# breakout_v3.net
KiCad netlist of a schematic drawn in EAGLE
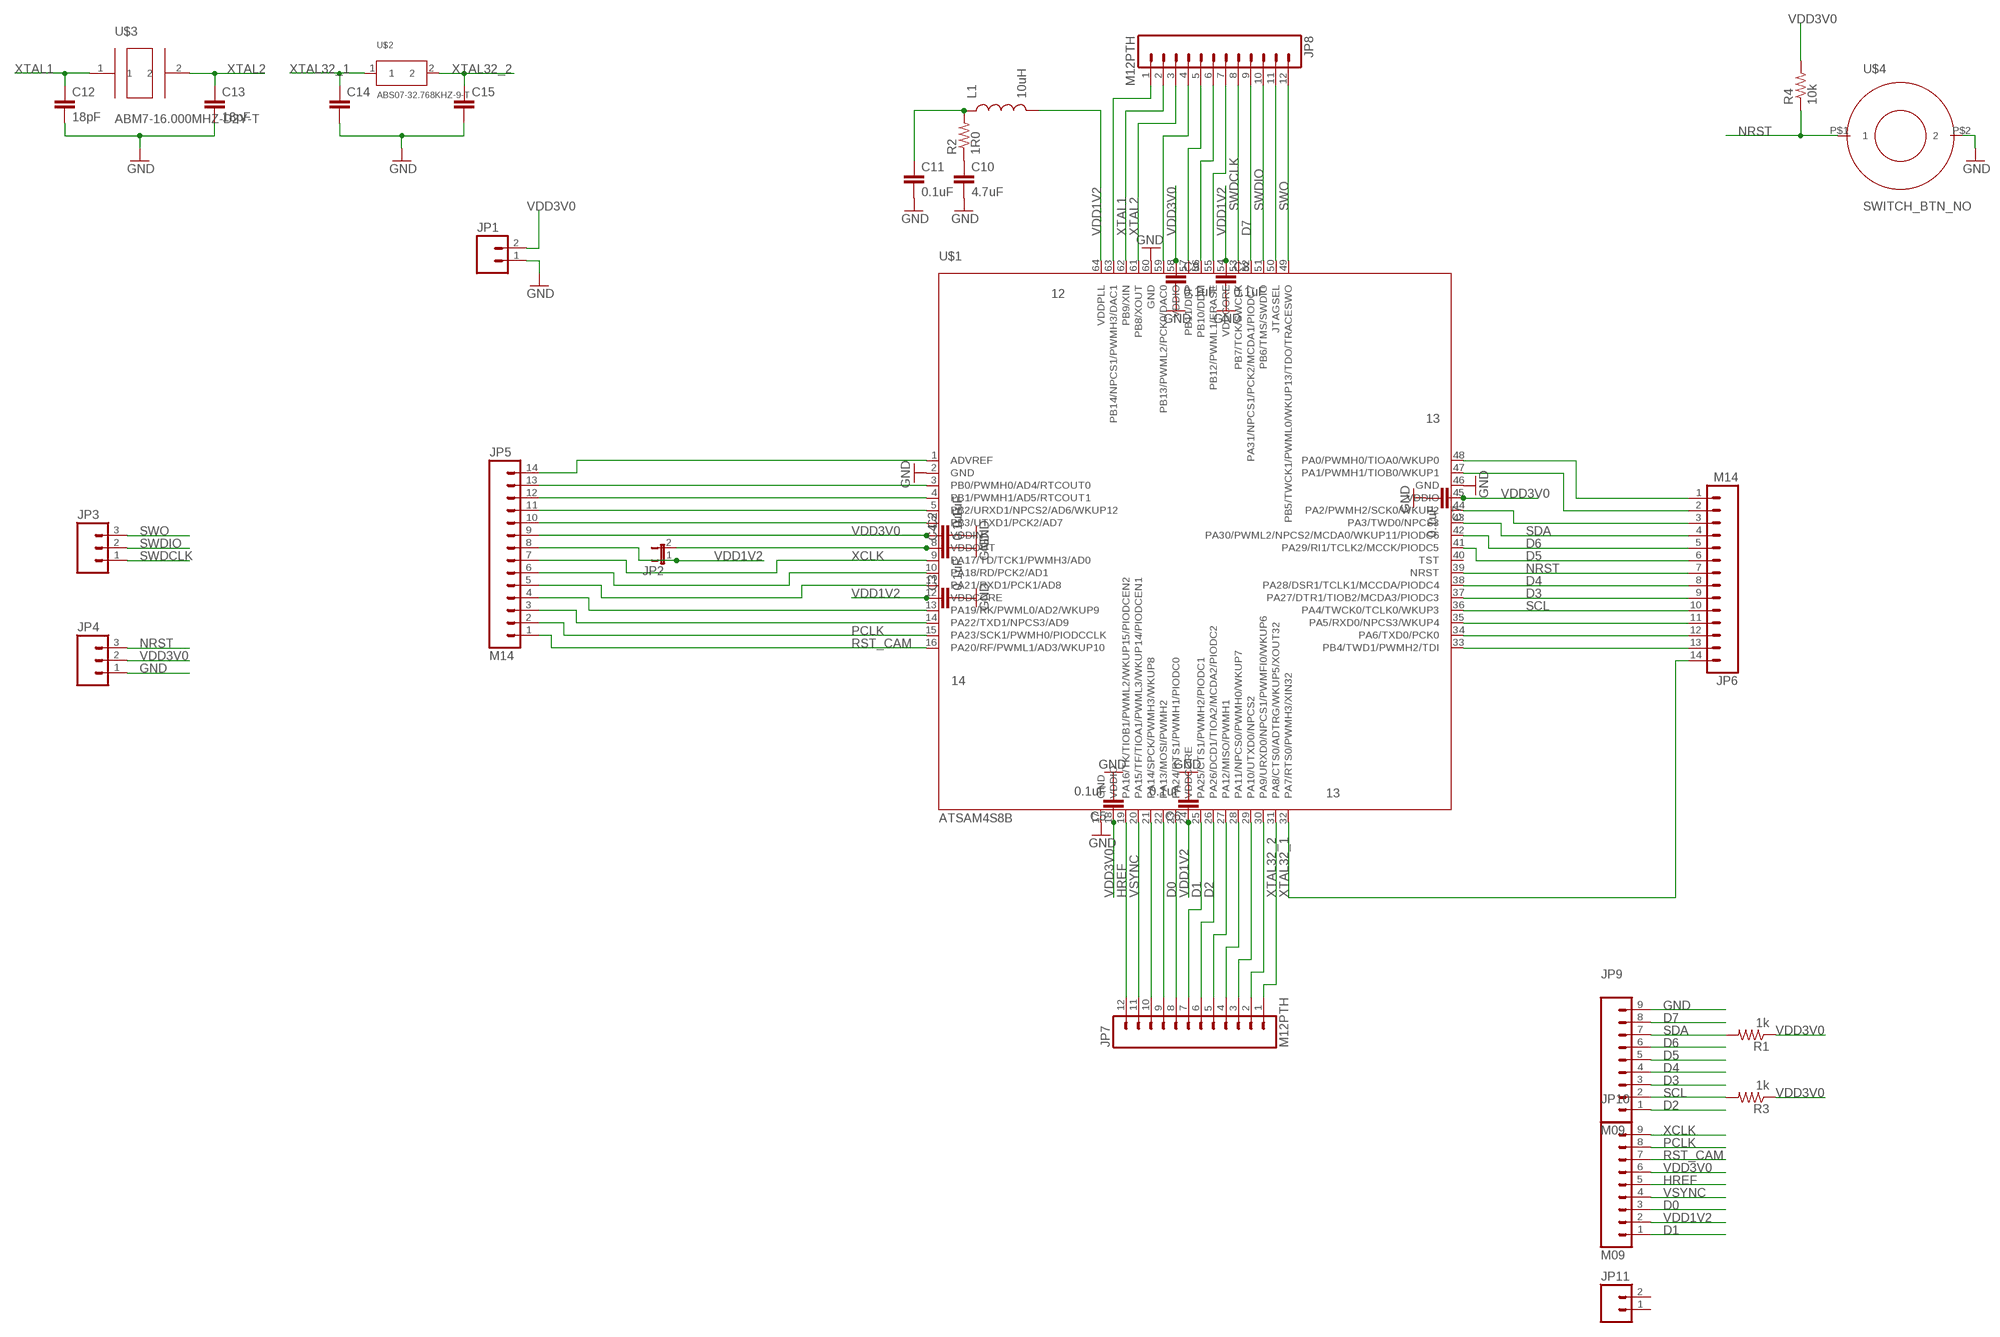
[diagram p0: schematic, sheet 1]

(export (version "E")
  (design (tool "Eeschema 10.0.6"))
  (components
    (comp (ref "C2")
      (value "0.1uF")
      (footprint "eagle-import:0805")
      (libsource (lib "eagle-import") (part "CAP0805"))
    )
    (comp (ref "C3")
      (value "0.1uF")
      (footprint "eagle-import:0805")
      (libsource (lib "eagle-import") (part "CAP0805"))
    )
    (comp (ref "C4")
      (value "0.1uF")
      (footprint "eagle-import:0805")
      (libsource (lib "eagle-import") (part "CAP0805"))
    )
    (comp (ref "C5")
      (value "0.1uF")
      (footprint "eagle-import:0805")
      (libsource (lib "eagle-import") (part "CAP0805"))
    )
    (comp (ref "C6")
      (value "0.1uF")
      (footprint "eagle-import:0805")
      (libsource (lib "eagle-import") (part "CAP0805"))
    )
    (comp (ref "C7")
      (value "0.1uF")
      (footprint "eagle-import:0805")
      (libsource (lib "eagle-import") (part "CAP0805"))
    )
    (comp (ref "C8")
      (value "0.1uF")
      (footprint "eagle-import:0805")
      (libsource (lib "eagle-import") (part "CAP0805"))
    )
    (comp (ref "C9")
      (value "0.1uF")
      (footprint "eagle-import:0805")
      (libsource (lib "eagle-import") (part "CAP0805"))
    )
    (comp (ref "C10")
      (value "4.7uF")
      (footprint "eagle-import:0805")
      (libsource (lib "eagle-import") (part "CAP0805"))
    )
    (comp (ref "C11")
      (value "0.1uF")
      (footprint "eagle-import:0805")
      (libsource (lib "eagle-import") (part "CAP0805"))
    )
    (comp (ref "C12")
      (value "18pF")
      (footprint "eagle-import:0805")
      (libsource (lib "eagle-import") (part "CAP0805"))
    )
    (comp (ref "C13")
      (value "18pF")
      (footprint "eagle-import:0805")
      (libsource (lib "eagle-import") (part "CAP0805"))
    )
    (comp (ref "C14")
      (value "CAP0805")
      (footprint "eagle-import:0805")
      (libsource (lib "eagle-import") (part "CAP0805"))
    )
    (comp (ref "C15")
      (value "CAP0805")
      (footprint "eagle-import:0805")
      (libsource (lib "eagle-import") (part "CAP0805"))
    )
    (comp (ref "JP1")
      (value "M02PTH")
      (footprint "eagle-import:1X02")
      (libsource (lib "eagle-import") (part "M02PTH"))
    )
    (comp (ref "JP2")
      (value "JUMPER-2PTH")
      (footprint "eagle-import:1X02")
      (libsource (lib "eagle-import") (part "JUMPER-2PTH"))
    )
    (comp (ref "JP3")
      (value "M03PTH")
      (footprint "eagle-import:1X03")
      (libsource (lib "eagle-import") (part "M03PTH"))
    )
    (comp (ref "JP4")
      (value "M03PTH")
      (footprint "eagle-import:1X03")
      (libsource (lib "eagle-import") (part "M03PTH"))
    )
    (comp (ref "JP5")
      (value "M14")
      (footprint "eagle-import:1X14")
      (libsource (lib "eagle-import") (part "M14"))
    )
    (comp (ref "JP6")
      (value "M14")
      (footprint "eagle-import:1X14")
      (libsource (lib "eagle-import") (part "M14"))
    )
    (comp (ref "JP7")
      (value "M12PTH")
      (footprint "eagle-import:1X12")
      (libsource (lib "eagle-import") (part "M12PTH"))
    )
    (comp (ref "JP8")
      (value "M12PTH")
      (footprint "eagle-import:1X12")
      (libsource (lib "eagle-import") (part "M12PTH"))
    )
    (comp (ref "JP9")
      (value "M09")
      (footprint "eagle-import:1X09")
      (libsource (lib "eagle-import") (part "M09"))
    )
    (comp (ref "JP10")
      (value "M09")
      (footprint "eagle-import:1X09")
      (libsource (lib "eagle-import") (part "M09"))
    )
    (comp (ref "JP11")
      (value "M02PTH")
      (footprint "eagle-import:1X02")
      (libsource (lib "eagle-import") (part "M02PTH"))
    )
    (comp (ref "L1")
      (value "10uH")
      (footprint "eagle-import:0805")
      (libsource (lib "eagle-import") (part "INDUCTOR0805"))
    )
    (comp (ref "R1")
      (value "1k")
      (footprint "eagle-import:0805")
      (libsource (lib "eagle-import") (part "RESISTOR0805-RES"))
    )
    (comp (ref "R2")
      (value "1R0")
      (footprint "eagle-import:0805")
      (libsource (lib "eagle-import") (part "RESISTOR0805-RES"))
    )
    (comp (ref "R3")
      (value "1k")
      (footprint "eagle-import:0805")
      (libsource (lib "eagle-import") (part "RESISTOR0805-RES"))
    )
    (comp (ref "R4")
      (value "10k")
      (footprint "eagle-import:0805")
      (libsource (lib "eagle-import") (part "RES"))
    )
    (comp (ref "U$1")
      (value "ATSAM4S8B")
      (footprint "eagle-import:QFP50P1200X1200X160-64N")
      (libsource (lib "eagle-import") (part "ATSAM4S8B"))
    )
    (comp (ref "U$2")
      (value "ABS07-32.768KHZ-9-T")
      (footprint "eagle-import:ABS07-32.768KHZ-9-T")
      (libsource (lib "eagle-import") (part "ABS07-32.768KHZ-9-T"))
    )
    (comp (ref "U$3")
      (value "ABM7-16.000MHZ-D2Y-T")
      (footprint "eagle-import:ABM7-16.000MHZ-D2Y-T")
      (libsource (lib "eagle-import") (part "ABM7-16.000MHZ-D2Y-T"))
    )
    (comp (ref "U$4")
      (value "SWITCH_BTN_NO")
      (footprint "eagle-import:BTN_2")
      (libsource (lib "eagle-import") (part "SWITCH_BTN_NO"))
    )
  )
  (nets
    (net (code "1") (name "/D0") (class "Default")
      (node (ref "JP10") (pin "3") (pinfunction "3_3") (pintype "passive"))
      (node (ref "JP7") (pin "8") (pinfunction "8_8") (pintype "passive"))
      (node (ref "U$1") (pin "23") (pinfunction "PA24/RTS1/PWMH1/PIODC0_23") (pintype "bidirectional"))
    )
    (net (code "2") (name "/D1") (class "Default")
      (node (ref "JP10") (pin "1") (pinfunction "1_1") (pintype "passive"))
      (node (ref "JP7") (pin "7") (pinfunction "7_7") (pintype "passive"))
      (node (ref "U$1") (pin "25") (pinfunction "PA25/CTS1/PWMH2/PIODC1_25") (pintype "bidirectional"))
    )
    (net (code "3") (name "/D2") (class "Default")
      (node (ref "JP7") (pin "6") (pinfunction "6_6") (pintype "passive"))
      (node (ref "JP9") (pin "1") (pinfunction "1_1") (pintype "passive"))
      (node (ref "U$1") (pin "26") (pinfunction "PA26/DCD1/TIOA2/MCDA2/PIODC2_26") (pintype "bidirectional"))
    )
    (net (code "4") (name "/D3") (class "Default")
      (node (ref "JP6") (pin "9") (pinfunction "9_9") (pintype "passive"))
      (node (ref "JP9") (pin "3") (pinfunction "3_3") (pintype "passive"))
      (node (ref "U$1") (pin "37") (pinfunction "PA27/DTR1/TIOB2/MCDA3/PIODC3_37") (pintype "bidirectional"))
    )
    (net (code "5") (name "/D4") (class "Default")
      (node (ref "JP6") (pin "8") (pinfunction "8_8") (pintype "passive"))
      (node (ref "JP9") (pin "4") (pinfunction "4_4") (pintype "passive"))
      (node (ref "U$1") (pin "38") (pinfunction "PA28/DSR1/TCLK1/MCCDA/PIODC4_38") (pintype "bidirectional"))
    )
    (net (code "6") (name "/D5") (class "Default")
      (node (ref "JP6") (pin "6") (pinfunction "6_6") (pintype "passive"))
      (node (ref "JP9") (pin "5") (pinfunction "5_5") (pintype "passive"))
      (node (ref "U$1") (pin "41") (pinfunction "PA29/RI1/TCLK2/MCCK/PIODC5_41") (pintype "bidirectional"))
    )
    (net (code "7") (name "/D6") (class "Default")
      (node (ref "JP6") (pin "5") (pinfunction "5_5") (pintype "passive"))
      (node (ref "JP9") (pin "6") (pinfunction "6_6") (pintype "passive"))
      (node (ref "U$1") (pin "42") (pinfunction "PA30/PWML2/NPCS2/MCDA0/WKUP11/PIODC6_42") (pintype "bidirectional"))
    )
    (net (code "8") (name "/D7") (class "Default")
      (node (ref "JP8") (pin "9") (pinfunction "9_9") (pintype "passive"))
      (node (ref "JP9") (pin "8") (pinfunction "8_8") (pintype "passive"))
      (node (ref "U$1") (pin "52") (pinfunction "PA31/NPCS1/PCK2/MCDA1/PIODC7_52") (pintype "bidirectional"))
    )
    (net (code "9") (name "/HREF") (class "Default")
      (node (ref "JP10") (pin "5") (pinfunction "5_5") (pintype "passive"))
      (node (ref "JP7") (pin "12") (pinfunction "12_12") (pintype "passive"))
      (node (ref "U$1") (pin "19") (pinfunction "PA16/TK/TIOB1/PWML2/WKUP15/PIODCEN2_19") (pintype "bidirectional"))
    )
    (net (code "10") (name "/NRST") (class "Default")
      (node (ref "JP4") (pin "3") (pinfunction "3_3") (pintype "passive"))
      (node (ref "JP6") (pin "7") (pinfunction "7_7") (pintype "passive"))
      (node (ref "R4") (pin "1") (pinfunction "1_1") (pintype "passive"))
      (node (ref "U$1") (pin "39") (pinfunction "NRST_39") (pintype "bidirectional"))
      (node (ref "U$4") (pin "P$1") (pinfunction "1_P$1") (pintype "bidirectional"))
    )
    (net (code "11") (name "/PCLK") (class "Default")
      (node (ref "JP10") (pin "8") (pinfunction "8_8") (pintype "passive"))
      (node (ref "JP5") (pin "2") (pinfunction "2_2") (pintype "passive"))
      (node (ref "U$1") (pin "15") (pinfunction "PA23/SCK1/PWMH0/PIODCCLK_15") (pintype "bidirectional"))
    )
    (net (code "12") (name "/RST_CAM") (class "Default")
      (node (ref "JP10") (pin "7") (pinfunction "7_7") (pintype "passive"))
      (node (ref "JP5") (pin "1") (pinfunction "1_1") (pintype "passive"))
      (node (ref "U$1") (pin "16") (pinfunction "PA20/RF/PWML1/AD3/WKUP10_16") (pintype "bidirectional"))
    )
    (net (code "13") (name "/SCL") (class "Default")
      (node (ref "JP6") (pin "10") (pinfunction "10_10") (pintype "passive"))
      (node (ref "JP9") (pin "2") (pinfunction "2_2") (pintype "passive"))
      (node (ref "R3") (pin "2") (pinfunction "2_2") (pintype "passive"))
      (node (ref "U$1") (pin "36") (pinfunction "PA4/TWCK0/TCLK0/WKUP3_36") (pintype "bidirectional"))
    )
    (net (code "14") (name "/SDA") (class "Default")
      (node (ref "JP6") (pin "4") (pinfunction "4_4") (pintype "passive"))
      (node (ref "JP9") (pin "7") (pinfunction "7_7") (pintype "passive"))
      (node (ref "R1") (pin "2") (pinfunction "2_2") (pintype "passive"))
      (node (ref "U$1") (pin "43") (pinfunction "PA3/TWD0/NPCS3_43") (pintype "bidirectional"))
    )
    (net (code "15") (name "/SWDCLK") (class "Default")
      (node (ref "JP3") (pin "1") (pinfunction "1_1") (pintype "passive"))
      (node (ref "JP8") (pin "8") (pinfunction "8_8") (pintype "passive"))
      (node (ref "U$1") (pin "53") (pinfunction "PB7/TCK/SWCLK_53") (pintype "bidirectional"))
    )
    (net (code "16") (name "/SWDIO") (class "Default")
      (node (ref "JP3") (pin "2") (pinfunction "2_2") (pintype "passive"))
      (node (ref "JP8") (pin "10") (pinfunction "10_10") (pintype "passive"))
      (node (ref "U$1") (pin "51") (pinfunction "PB6/TMS/SWDIO_51") (pintype "bidirectional"))
    )
    (net (code "17") (name "/SWO") (class "Default")
      (node (ref "JP3") (pin "3") (pinfunction "3_3") (pintype "passive"))
      (node (ref "JP8") (pin "12") (pinfunction "12_12") (pintype "passive"))
      (node (ref "U$1") (pin "49") (pinfunction "PB5/TWCK1/PWML0/WKUP13/TDO/TRACESWO_49") (pintype "bidirectional"))
    )
    (net (code "18") (name "/VDD1V2") (class "Default")
      (node (ref "C3") (pin "1") (pinfunction "1_1") (pintype "passive"))
      (node (ref "C6") (pin "1") (pinfunction "1_1") (pintype "passive"))
      (node (ref "C8") (pin "1") (pinfunction "1_1") (pintype "passive"))
      (node (ref "JP10") (pin "2") (pinfunction "2_2") (pintype "passive"))
      (node (ref "JP2") (pin "1") (pinfunction "1_1") (pintype "passive"))
      (node (ref "JP5") (pin "8") (pinfunction "8_8") (pintype "passive"))
      (node (ref "L1") (pin "2") (pinfunction "2_2") (pintype "passive"))
      (node (ref "U$1") (pin "12") (pinfunction "VDDCORE_12") (pintype "bidirectional"))
      (node (ref "U$1") (pin "24") (pinfunction "VDDCORE_24") (pintype "bidirectional"))
      (node (ref "U$1") (pin "54") (pinfunction "VDDCORE_54") (pintype "bidirectional"))
      (node (ref "U$1") (pin "64") (pinfunction "VDDPLL_64") (pintype "bidirectional"))
    )
    (net (code "19") (name "/VDD3V0") (class "Default")
      (node (ref "C2") (pin "1") (pinfunction "1_1") (pintype "passive"))
      (node (ref "C5") (pin "1") (pinfunction "1_1") (pintype "passive"))
      (node (ref "C7") (pin "1") (pinfunction "1_1") (pintype "passive"))
      (node (ref "C9") (pin "1") (pinfunction "1_1") (pintype "passive"))
      (node (ref "JP1") (pin "2") (pinfunction "2_2") (pintype "passive"))
      (node (ref "JP10") (pin "6") (pinfunction "6_6") (pintype "passive"))
      (node (ref "JP4") (pin "2") (pinfunction "2_2") (pintype "passive"))
      (node (ref "JP5") (pin "9") (pinfunction "9_9") (pintype "passive"))
      (node (ref "R1") (pin "1") (pinfunction "1_1") (pintype "passive"))
      (node (ref "R3") (pin "1") (pinfunction "1_1") (pintype "passive"))
      (node (ref "R4") (pin "2") (pinfunction "2_2") (pintype "passive"))
      (node (ref "U$1") (pin "18") (pinfunction "VDDIO_18") (pintype "bidirectional"))
      (node (ref "U$1") (pin "45") (pinfunction "VDDIO_45") (pintype "bidirectional"))
      (node (ref "U$1") (pin "58") (pinfunction "VDDIO_58") (pintype "bidirectional"))
      (node (ref "U$1") (pin "7") (pinfunction "VDDIN_7") (pintype "bidirectional"))
    )
    (net (code "20") (name "/VSYNC") (class "Default")
      (node (ref "JP10") (pin "4") (pinfunction "4_4") (pintype "passive"))
      (node (ref "JP7") (pin "11") (pinfunction "11_11") (pintype "passive"))
      (node (ref "U$1") (pin "20") (pinfunction "PA15/TF/TIOA1/PWML3/WKUP14/PIODCEN1_20") (pintype "bidirectional"))
    )
    (net (code "21") (name "/XCLK") (class "Default")
      (node (ref "JP10") (pin "9") (pinfunction "9_9") (pintype "passive"))
      (node (ref "JP5") (pin "7") (pinfunction "7_7") (pintype "passive"))
      (node (ref "U$1") (pin "9") (pinfunction "PA17/TD/TCK1/PWMH3/AD0_9") (pintype "bidirectional"))
    )
    (net (code "22") (name "/XTAL1") (class "Default")
      (node (ref "C12") (pin "1") (pinfunction "1_1") (pintype "passive"))
      (node (ref "JP8") (pin "2") (pinfunction "2_2") (pintype "passive"))
      (node (ref "U$1") (pin "62") (pinfunction "PB9/XIN_62") (pintype "bidirectional"))
      (node (ref "U$3") (pin "1") (pinfunction "1_1") (pintype "bidirectional"))
    )
    (net (code "23") (name "/XTAL2") (class "Default")
      (node (ref "C13") (pin "1") (pinfunction "1_1") (pintype "passive"))
      (node (ref "JP8") (pin "3") (pinfunction "3_3") (pintype "passive"))
      (node (ref "U$1") (pin "61") (pinfunction "PB8/XOUT_61") (pintype "bidirectional"))
      (node (ref "U$3") (pin "2") (pinfunction "2_2") (pintype "bidirectional"))
    )
    (net (code "24") (name "/XTAL32_1") (class "Default")
      (node (ref "C14") (pin "1") (pinfunction "1_1") (pintype "passive"))
      (node (ref "JP6") (pin "14") (pinfunction "14_14") (pintype "passive"))
      (node (ref "U$1") (pin "32") (pinfunction "PA7/RTS0/PWMH3/XIN32_32") (pintype "bidirectional"))
      (node (ref "U$2") (pin "1") (pinfunction "1_1") (pintype "bidirectional"))
    )
    (net (code "25") (name "/XTAL32_2") (class "Default")
      (node (ref "C15") (pin "1") (pinfunction "1_1") (pintype "passive"))
      (node (ref "JP7") (pin "1") (pinfunction "1_1") (pintype "passive"))
      (node (ref "U$1") (pin "31") (pinfunction "PA8/CTS0/ADTRG/WKUP5/XOUT32_31") (pintype "bidirectional"))
      (node (ref "U$2") (pin "2") (pinfunction "2_2") (pintype "bidirectional"))
    )
    (net (code "26") (name "GND") (class "Default")
      (node (ref "C10") (pin "2") (pinfunction "2_2") (pintype "passive"))
      (node (ref "C11") (pin "2") (pinfunction "2_2") (pintype "passive"))
      (node (ref "C12") (pin "2") (pinfunction "2_2") (pintype "passive"))
      (node (ref "C13") (pin "2") (pinfunction "2_2") (pintype "passive"))
      (node (ref "C14") (pin "2") (pinfunction "2_2") (pintype "passive"))
      (node (ref "C15") (pin "2") (pinfunction "2_2") (pintype "passive"))
      (node (ref "C2") (pin "2") (pinfunction "2_2") (pintype "passive"))
      (node (ref "C3") (pin "2") (pinfunction "2_2") (pintype "passive"))
      (node (ref "C4") (pin "2") (pinfunction "2_2") (pintype "passive"))
      (node (ref "C5") (pin "2") (pinfunction "2_2") (pintype "passive"))
      (node (ref "C6") (pin "2") (pinfunction "2_2") (pintype "passive"))
      (node (ref "C7") (pin "2") (pinfunction "2_2") (pintype "passive"))
      (node (ref "C8") (pin "2") (pinfunction "2_2") (pintype "passive"))
      (node (ref "C9") (pin "2") (pinfunction "2_2") (pintype "passive"))
      (node (ref "JP1") (pin "1") (pinfunction "1_1") (pintype "passive"))
      (node (ref "JP4") (pin "1") (pinfunction "1_1") (pintype "passive"))
      (node (ref "JP9") (pin "9") (pinfunction "9_9") (pintype "passive"))
      (node (ref "U$1") (pin "17") (pinfunction "GND_17") (pintype "bidirectional"))
      (node (ref "U$1") (pin "2") (pinfunction "GND_2") (pintype "bidirectional"))
      (node (ref "U$1") (pin "46") (pinfunction "GND_46") (pintype "bidirectional"))
      (node (ref "U$1") (pin "60") (pinfunction "GND_60") (pintype "bidirectional"))
      (node (ref "U$4") (pin "P$2") (pinfunction "2_P$2") (pintype "bidirectional"))
    )
    (net (code "27") (name "Net-(C10-Pad1)") (class "Default")
      (node (ref "C10") (pin "1") (pinfunction "1_1") (pintype "passive"))
      (node (ref "R2") (pin "1") (pinfunction "1_1") (pintype "passive"))
    )
    (net (code "28") (name "Net-(C11-Pad1)") (class "Default")
      (node (ref "C11") (pin "1") (pinfunction "1_1") (pintype "passive"))
      (node (ref "L1") (pin "1") (pinfunction "1_1") (pintype "passive"))
      (node (ref "R2") (pin "2") (pinfunction "2_2") (pintype "passive"))
    )
    (net (code "29") (name "Net-(U$1-ADVREF)") (class "Default")
      (node (ref "JP5") (pin "14") (pinfunction "14_14") (pintype "passive"))
      (node (ref "U$1") (pin "1") (pinfunction "ADVREF_1") (pintype "bidirectional"))
    )
    (net (code "30") (name "Net-(U$1-JTAGSEL)") (class "Default")
      (node (ref "JP8") (pin "11") (pinfunction "11_11") (pintype "passive"))
      (node (ref "U$1") (pin "50") (pinfunction "JTAGSEL_50") (pintype "bidirectional"))
    )
    (net (code "31") (name "Net-(U$1-PA0{slash}PWMH0{slash}TIOA0{slash}WKUP0)") (class "Default")
      (node (ref "JP6") (pin "1") (pinfunction "1_1") (pintype "passive"))
      (node (ref "U$1") (pin "48") (pinfunction "PA0/PWMH0/TIOA0/WKUP0_48") (pintype "bidirectional"))
    )
    (net (code "32") (name "Net-(U$1-PA1{slash}PWMH1{slash}TIOB0{slash}WKUP1)") (class "Default")
      (node (ref "JP6") (pin "2") (pinfunction "2_2") (pintype "passive"))
      (node (ref "U$1") (pin "47") (pinfunction "PA1/PWMH1/TIOB0/WKUP1_47") (pintype "bidirectional"))
    )
    (net (code "33") (name "Net-(U$1-PA2{slash}PWMH2{slash}SCK0{slash}WKUP2)") (class "Default")
      (node (ref "JP6") (pin "3") (pinfunction "3_3") (pintype "passive"))
      (node (ref "U$1") (pin "44") (pinfunction "PA2/PWMH2/SCK0/WKUP2_44") (pintype "bidirectional"))
    )
    (net (code "34") (name "Net-(U$1-PA5{slash}RXD0{slash}NPCS3{slash}WKUP4)") (class "Default")
      (node (ref "JP6") (pin "11") (pinfunction "11_11") (pintype "passive"))
      (node (ref "U$1") (pin "35") (pinfunction "PA5/RXD0/NPCS3/WKUP4_35") (pintype "bidirectional"))
    )
    (net (code "35") (name "Net-(U$1-PA6{slash}TXD0{slash}PCK0)") (class "Default")
      (node (ref "JP6") (pin "12") (pinfunction "12_12") (pintype "passive"))
      (node (ref "U$1") (pin "34") (pinfunction "PA6/TXD0/PCK0_34") (pintype "bidirectional"))
    )
    (net (code "36") (name "Net-(U$1-PA9{slash}URXD0{slash}NPCS1{slash}PWMFI0{slash}WKUP6)") (class "Default")
      (node (ref "JP7") (pin "2") (pinfunction "2_2") (pintype "passive"))
      (node (ref "U$1") (pin "30") (pinfunction "PA9/URXD0/NPCS1/PWMFI0/WKUP6_30") (pintype "bidirectional"))
    )
    (net (code "37") (name "Net-(U$1-PA10{slash}UTXD0{slash}NPCS2)") (class "Default")
      (node (ref "JP7") (pin "3") (pinfunction "3_3") (pintype "passive"))
      (node (ref "U$1") (pin "29") (pinfunction "PA10/UTXD0/NPCS2_29") (pintype "bidirectional"))
    )
    (net (code "38") (name "Net-(U$1-PA11{slash}NPCS0{slash}PWMH0{slash}WKUP7)") (class "Default")
      (node (ref "JP7") (pin "4") (pinfunction "4_4") (pintype "passive"))
      (node (ref "U$1") (pin "28") (pinfunction "PA11/NPCS0/PWMH0/WKUP7_28") (pintype "bidirectional"))
    )
    (net (code "39") (name "Net-(U$1-PA12{slash}MISO{slash}PWMH1)") (class "Default")
      (node (ref "JP7") (pin "5") (pinfunction "5_5") (pintype "passive"))
      (node (ref "U$1") (pin "27") (pinfunction "PA12/MISO/PWMH1_27") (pintype "bidirectional"))
    )
    (net (code "40") (name "Net-(U$1-PA13{slash}MOSI{slash}PWMH2)") (class "Default")
      (node (ref "JP7") (pin "9") (pinfunction "9_9") (pintype "passive"))
      (node (ref "U$1") (pin "22") (pinfunction "PA13/MOSI/PWMH2_22") (pintype "bidirectional"))
    )
    (net (code "41") (name "Net-(U$1-PA14{slash}SPCK{slash}PWMH3{slash}WKUP8)") (class "Default")
      (node (ref "JP7") (pin "10") (pinfunction "10_10") (pintype "passive"))
      (node (ref "U$1") (pin "21") (pinfunction "PA14/SPCK/PWMH3/WKUP8_21") (pintype "bidirectional"))
    )
    (net (code "42") (name "Net-(U$1-PA18{slash}RD{slash}PCK2{slash}AD1)") (class "Default")
      (node (ref "JP5") (pin "6") (pinfunction "6_6") (pintype "passive"))
      (node (ref "U$1") (pin "10") (pinfunction "PA18/RD/PCK2/AD1_10") (pintype "bidirectional"))
    )
    (net (code "43") (name "Net-(U$1-PA19{slash}RK{slash}PWML0{slash}AD2{slash}WKUP9)") (class "Default")
      (node (ref "JP5") (pin "4") (pinfunction "4_4") (pintype "passive"))
      (node (ref "U$1") (pin "13") (pinfunction "PA19/RK/PWML0/AD2/WKUP9_13") (pintype "bidirectional"))
    )
    (net (code "44") (name "Net-(U$1-PA21{slash}RXD1{slash}PCK1{slash}AD8)") (class "Default")
      (node (ref "JP5") (pin "5") (pinfunction "5_5") (pintype "passive"))
      (node (ref "U$1") (pin "11") (pinfunction "PA21/RXD1/PCK1/AD8_11") (pintype "bidirectional"))
    )
    (net (code "45") (name "Net-(U$1-PA22{slash}TXD1{slash}NPCS3{slash}AD9)") (class "Default")
      (node (ref "JP5") (pin "3") (pinfunction "3_3") (pintype "passive"))
      (node (ref "U$1") (pin "14") (pinfunction "PA22/TXD1/NPCS3/AD9_14") (pintype "bidirectional"))
    )
    (net (code "46") (name "Net-(U$1-PB0{slash}PWMH0{slash}AD4{slash}RTCOUT0)") (class "Default")
      (node (ref "JP5") (pin "13") (pinfunction "13_13") (pintype "passive"))
      (node (ref "U$1") (pin "3") (pinfunction "PB0/PWMH0/AD4/RTCOUT0_3") (pintype "bidirectional"))
    )
    (net (code "47") (name "Net-(U$1-PB1{slash}PWMH1{slash}AD5{slash}RTCOUT1)") (class "Default")
      (node (ref "JP5") (pin "12") (pinfunction "12_12") (pintype "passive"))
      (node (ref "U$1") (pin "4") (pinfunction "PB1/PWMH1/AD5/RTCOUT1_4") (pintype "bidirectional"))
    )
    (net (code "48") (name "Net-(U$1-PB2{slash}URXD1{slash}NPCS2{slash}AD6{slash}WKUP12)") (class "Default")
      (node (ref "JP5") (pin "11") (pinfunction "11_11") (pintype "passive"))
      (node (ref "U$1") (pin "5") (pinfunction "PB2/URXD1/NPCS2/AD6/WKUP12_5") (pintype "bidirectional"))
    )
    (net (code "49") (name "Net-(U$1-PB3{slash}UTXD1{slash}PCK2{slash}AD7)") (class "Default")
      (node (ref "JP5") (pin "10") (pinfunction "10_10") (pintype "passive"))
      (node (ref "U$1") (pin "6") (pinfunction "PB3/UTXD1/PCK2/AD7_6") (pintype "bidirectional"))
    )
    (net (code "50") (name "Net-(U$1-PB4{slash}TWD1{slash}PWMH2{slash}TDI)") (class "Default")
      (node (ref "JP6") (pin "13") (pinfunction "13_13") (pintype "passive"))
      (node (ref "U$1") (pin "33") (pinfunction "PB4/TWD1/PWMH2/TDI_33") (pintype "bidirectional"))
    )
    (net (code "51") (name "Net-(U$1-PB10{slash}DDM)") (class "Default")
      (node (ref "JP8") (pin "6") (pinfunction "6_6") (pintype "passive"))
      (node (ref "U$1") (pin "56") (pinfunction "PB10/DDM_56") (pintype "bidirectional"))
    )
    (net (code "52") (name "Net-(U$1-PB11{slash}DDP)") (class "Default")
      (node (ref "JP8") (pin "5") (pinfunction "5_5") (pintype "passive"))
      (node (ref "U$1") (pin "57") (pinfunction "PB11/DDP_57") (pintype "bidirectional"))
    )
    (net (code "53") (name "Net-(U$1-PB12{slash}PWML1{slash}ERASE)") (class "Default")
      (node (ref "JP8") (pin "7") (pinfunction "7_7") (pintype "passive"))
      (node (ref "U$1") (pin "55") (pinfunction "PB12/PWML1/ERASE_55") (pintype "bidirectional"))
    )
    (net (code "54") (name "Net-(U$1-PB13{slash}PWML2{slash}PCK0{slash}DAC0)") (class "Default")
      (node (ref "JP8") (pin "4") (pinfunction "4_4") (pintype "passive"))
      (node (ref "U$1") (pin "59") (pinfunction "PB13/PWML2/PCK0/DAC0_59") (pintype "bidirectional"))
    )
    (net (code "55") (name "Net-(U$1-PB14{slash}NPCS1{slash}PWMH3{slash}DAC1)") (class "Default")
      (node (ref "JP8") (pin "1") (pinfunction "1_1") (pintype "passive"))
      (node (ref "U$1") (pin "63") (pinfunction "PB14/NPCS1/PWMH3/DAC1_63") (pintype "bidirectional"))
    )
    (net (code "56") (name "Net-(U$1-VDDOUT)") (class "Default")
      (node (ref "C4") (pin "1") (pinfunction "1_1") (pintype "passive"))
      (node (ref "JP2") (pin "2") (pinfunction "2_2") (pintype "passive"))
      (node (ref "U$1") (pin "8") (pinfunction "VDDOUT_8") (pintype "bidirectional"))
    )
    (net (code "57") (name "unconnected-(JP11-Pad1)") (class "Default")
      (node (ref "JP11") (pin "1") (pinfunction "1_1") (pintype "passive"))
    )
    (net (code "58") (name "unconnected-(JP11-Pad2)") (class "Default")
      (node (ref "JP11") (pin "2") (pinfunction "2_2") (pintype "passive"))
    )
    (net (code "59") (name "unconnected-(U$1-TST-Pad40)") (class "Default")
      (node (ref "U$1") (pin "40") (pinfunction "TST_40") (pintype "bidirectional"))
    )
  )
)
